# LED_STATUS.net
KiCad netlist of a schematic drawn in Altium Designer
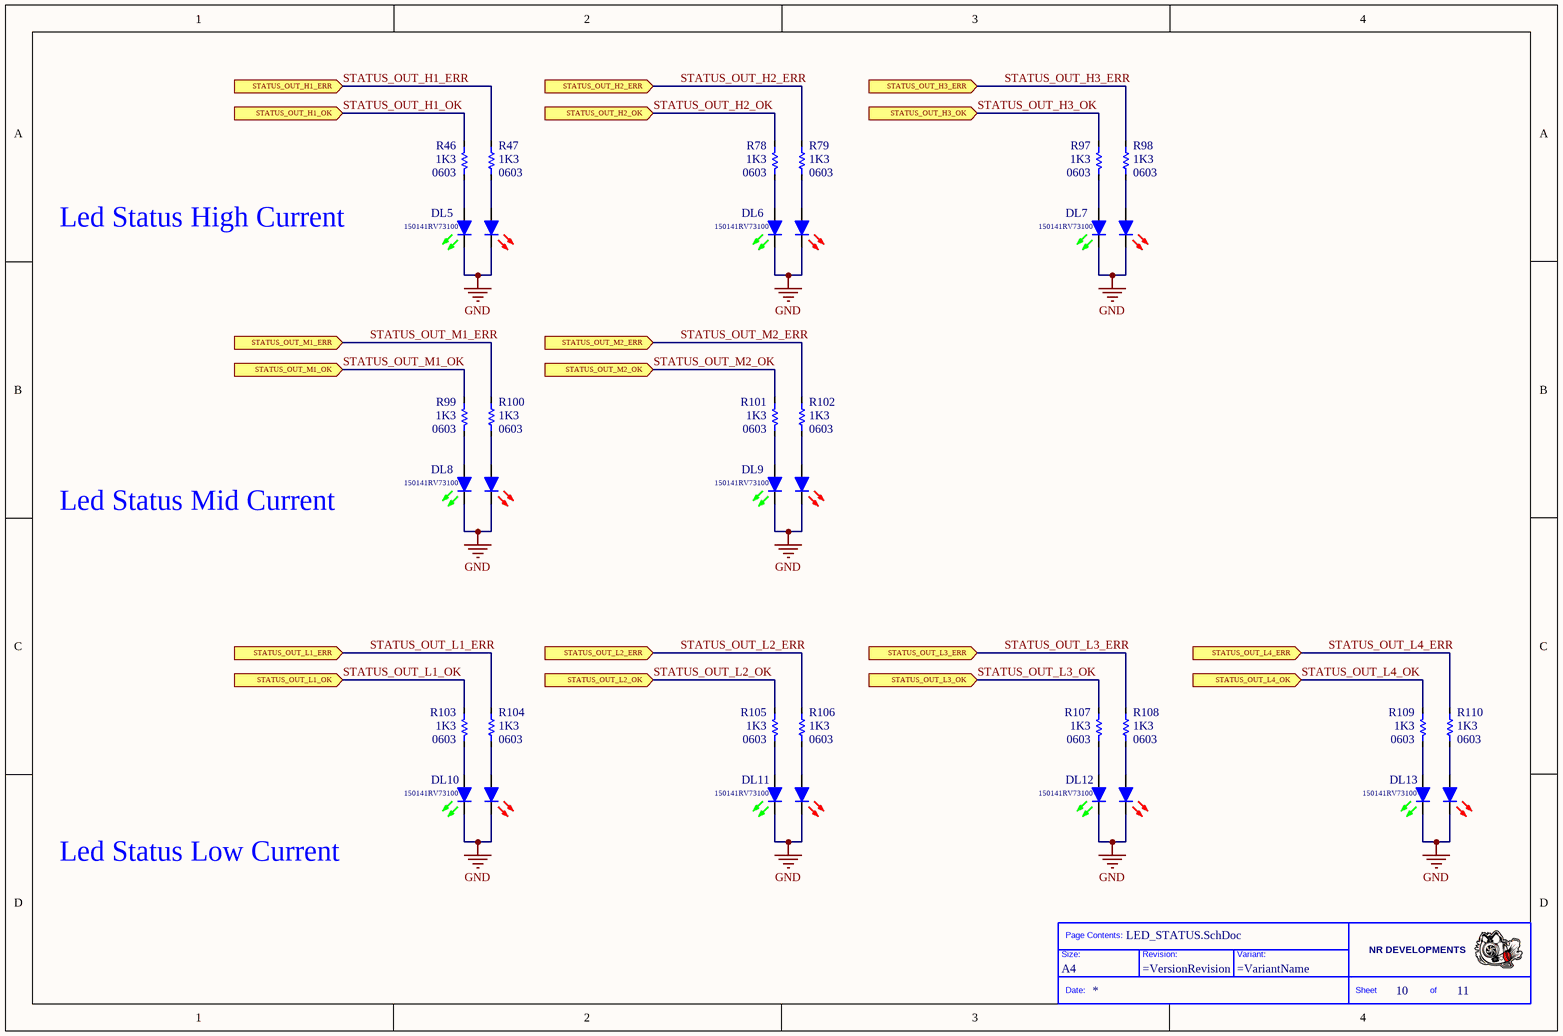
[diagram p0: LED_STATUS.SchDoc]

(export (version "E")
  (design (tool "Eeschema 10.0.6"))
  (components
    (comp (ref "*")
      (value "Title_Block")
      (fields (field (name "SIZE") "A4"))
      (libsource (lib "My_LIB") (part "Title_Block"))
    )
    (comp (ref "DL5")
      (value "150141RV73100")
      (footprint "WURTH-SBTW_3528")
      (description "Led Red - Green 3528")
      (fields (field (name "MANUFACTURER") "Wurth") (field (name "Comment") "LED_Red_Green"))
      (libsource (lib "My_LIB") (part "LED_Red_Green"))
    )
    (comp (ref "DL6")
      (value "150141RV73100")
      (footprint "WURTH-SBTW_3528")
      (description "Led Red - Green 3528")
      (fields (field (name "MANUFACTURER") "Wurth") (field (name "Comment") "LED_Red_Green"))
      (libsource (lib "My_LIB") (part "LED_Red_Green"))
    )
    (comp (ref "DL7")
      (value "150141RV73100")
      (footprint "WURTH-SBTW_3528")
      (description "Led Red - Green 3528")
      (fields (field (name "MANUFACTURER") "Wurth") (field (name "Comment") "LED_Red_Green"))
      (libsource (lib "My_LIB") (part "LED_Red_Green"))
    )
    (comp (ref "DL8")
      (value "150141RV73100")
      (footprint "WURTH-SBTW_3528")
      (description "Led Red - Green 3528")
      (fields (field (name "MANUFACTURER") "Wurth") (field (name "Comment") "LED_Red_Green"))
      (libsource (lib "My_LIB") (part "LED_Red_Green"))
    )
    (comp (ref "DL9")
      (value "150141RV73100")
      (footprint "WURTH-SBTW_3528")
      (description "Led Red - Green 3528")
      (fields (field (name "MANUFACTURER") "Wurth") (field (name "Comment") "LED_Red_Green"))
      (libsource (lib "My_LIB") (part "LED_Red_Green"))
    )
    (comp (ref "DL10")
      (value "150141RV73100")
      (footprint "WURTH-SBTW_3528")
      (description "Led Red - Green 3528")
      (fields (field (name "MANUFACTURER") "Wurth") (field (name "Comment") "LED_Red_Green"))
      (libsource (lib "My_LIB") (part "LED_Red_Green"))
    )
    (comp (ref "DL11")
      (value "150141RV73100")
      (footprint "WURTH-SBTW_3528")
      (description "Led Red - Green 3528")
      (fields (field (name "MANUFACTURER") "Wurth") (field (name "Comment") "LED_Red_Green"))
      (libsource (lib "My_LIB") (part "LED_Red_Green"))
    )
    (comp (ref "DL12")
      (value "150141RV73100")
      (footprint "WURTH-SBTW_3528")
      (description "Led Red - Green 3528")
      (fields (field (name "MANUFACTURER") "Wurth") (field (name "Comment") "LED_Red_Green"))
      (libsource (lib "My_LIB") (part "LED_Red_Green"))
    )
    (comp (ref "DL13")
      (value "150141RV73100")
      (footprint "WURTH-SBTW_3528")
      (description "Led Red - Green 3528")
      (fields (field (name "MANUFACTURER") "Wurth") (field (name "Comment") "LED_Red_Green"))
      (libsource (lib "My_LIB") (part "LED_Red_Green"))
    )
    (comp (ref "R46")
      (value "1K3")
      (footprint "RESC1608X06M")
      (fields
        (field (name "CASE") "0603")
        (field (name "MANUFACTURER") "Vishay")
        (field (name "PARTNUMBER") "RC0603FR-071K3L")
        (field (name "Comment") "Res")
      )
      (libsource (lib "My_LIB") (part "Resistor"))
    )
    (comp (ref "R47")
      (value "1K3")
      (footprint "RESC1608X06M")
      (fields
        (field (name "CASE") "0603")
        (field (name "MANUFACTURER") "Vishay")
        (field (name "PARTNUMBER") "RC0603FR-071K3L")
        (field (name "Comment") "Res")
      )
      (libsource (lib "My_LIB") (part "Resistor"))
    )
    (comp (ref "R78")
      (value "1K3")
      (footprint "RESC1608X06M")
      (fields
        (field (name "CASE") "0603")
        (field (name "MANUFACTURER") "Vishay")
        (field (name "PARTNUMBER") "RC0603FR-071K3L")
        (field (name "Comment") "Res")
      )
      (libsource (lib "My_LIB") (part "Resistor"))
    )
    (comp (ref "R79")
      (value "1K3")
      (footprint "RESC1608X06M")
      (fields
        (field (name "CASE") "0603")
        (field (name "MANUFACTURER") "Vishay")
        (field (name "PARTNUMBER") "RC0603FR-071K3L")
        (field (name "Comment") "Res")
      )
      (libsource (lib "My_LIB") (part "Resistor"))
    )
    (comp (ref "R97")
      (value "1K3")
      (footprint "RESC1608X06M")
      (fields
        (field (name "CASE") "0603")
        (field (name "MANUFACTURER") "Vishay")
        (field (name "PARTNUMBER") "RC0603FR-071K3L")
        (field (name "Comment") "Res")
      )
      (libsource (lib "My_LIB") (part "Resistor"))
    )
    (comp (ref "R98")
      (value "1K3")
      (footprint "RESC1608X06M")
      (fields
        (field (name "CASE") "0603")
        (field (name "MANUFACTURER") "Vishay")
        (field (name "PARTNUMBER") "RC0603FR-071K3L")
        (field (name "Comment") "Res")
      )
      (libsource (lib "My_LIB") (part "Resistor"))
    )
    (comp (ref "R99")
      (value "1K3")
      (footprint "RESC1608X06M")
      (fields
        (field (name "CASE") "0603")
        (field (name "MANUFACTURER") "Vishay")
        (field (name "PARTNUMBER") "RC0603FR-071K3L")
        (field (name "Comment") "Res")
      )
      (libsource (lib "My_LIB") (part "Resistor"))
    )
    (comp (ref "R100")
      (value "1K3")
      (footprint "RESC1608X06M")
      (fields
        (field (name "CASE") "0603")
        (field (name "MANUFACTURER") "Vishay")
        (field (name "PARTNUMBER") "RC0603FR-071K3L")
        (field (name "Comment") "Res")
      )
      (libsource (lib "My_LIB") (part "Resistor"))
    )
    (comp (ref "R101")
      (value "1K3")
      (footprint "RESC1608X06M")
      (fields
        (field (name "CASE") "0603")
        (field (name "MANUFACTURER") "Vishay")
        (field (name "PARTNUMBER") "RC0603FR-071K3L")
        (field (name "Comment") "Res")
      )
      (libsource (lib "My_LIB") (part "Resistor"))
    )
    (comp (ref "R102")
      (value "1K3")
      (footprint "RESC1608X06M")
      (fields
        (field (name "CASE") "0603")
        (field (name "MANUFACTURER") "Vishay")
        (field (name "PARTNUMBER") "RC0603FR-071K3L")
        (field (name "Comment") "Res")
      )
      (libsource (lib "My_LIB") (part "Resistor"))
    )
    (comp (ref "R103")
      (value "1K3")
      (footprint "RESC1608X06M")
      (fields
        (field (name "CASE") "0603")
        (field (name "MANUFACTURER") "Vishay")
        (field (name "PARTNUMBER") "RC0603FR-071K3L")
        (field (name "Comment") "Res")
      )
      (libsource (lib "My_LIB") (part "Resistor"))
    )
    (comp (ref "R104")
      (value "1K3")
      (footprint "RESC1608X06M")
      (fields
        (field (name "CASE") "0603")
        (field (name "MANUFACTURER") "Vishay")
        (field (name "PARTNUMBER") "RC0603FR-071K3L")
        (field (name "Comment") "Res")
      )
      (libsource (lib "My_LIB") (part "Resistor"))
    )
    (comp (ref "R105")
      (value "1K3")
      (footprint "RESC1608X06M")
      (fields
        (field (name "CASE") "0603")
        (field (name "MANUFACTURER") "Vishay")
        (field (name "PARTNUMBER") "RC0603FR-071K3L")
        (field (name "Comment") "Res")
      )
      (libsource (lib "My_LIB") (part "Resistor"))
    )
    (comp (ref "R106")
      (value "1K3")
      (footprint "RESC1608X06M")
      (fields
        (field (name "CASE") "0603")
        (field (name "MANUFACTURER") "Vishay")
        (field (name "PARTNUMBER") "RC0603FR-071K3L")
        (field (name "Comment") "Res")
      )
      (libsource (lib "My_LIB") (part "Resistor"))
    )
    (comp (ref "R107")
      (value "1K3")
      (footprint "RESC1608X06M")
      (fields
        (field (name "CASE") "0603")
        (field (name "MANUFACTURER") "Vishay")
        (field (name "PARTNUMBER") "RC0603FR-071K3L")
        (field (name "Comment") "Res")
      )
      (libsource (lib "My_LIB") (part "Resistor"))
    )
    (comp (ref "R108")
      (value "1K3")
      (footprint "RESC1608X06M")
      (fields
        (field (name "CASE") "0603")
        (field (name "MANUFACTURER") "Vishay")
        (field (name "PARTNUMBER") "RC0603FR-071K3L")
        (field (name "Comment") "Res")
      )
      (libsource (lib "My_LIB") (part "Resistor"))
    )
    (comp (ref "R109")
      (value "1K3")
      (footprint "RESC1608X06M")
      (fields
        (field (name "CASE") "0603")
        (field (name "MANUFACTURER") "Vishay")
        (field (name "PARTNUMBER") "RC0603FR-071K3L")
        (field (name "Comment") "Res")
      )
      (libsource (lib "My_LIB") (part "Resistor"))
    )
    (comp (ref "R110")
      (value "1K3")
      (footprint "RESC1608X06M")
      (fields
        (field (name "CASE") "0603")
        (field (name "MANUFACTURER") "Vishay")
        (field (name "PARTNUMBER") "RC0603FR-071K3L")
        (field (name "Comment") "Res")
      )
      (libsource (lib "My_LIB") (part "Resistor"))
    )
  )
  (nets
    (net (code "1") (name "/STATUS_OUT_H1_ERR") (class "Default")
      (node (ref "R47") (pin "2") (pinfunction "2_2") (pintype "passive"))
    )
    (net (code "2") (name "/STATUS_OUT_H1_OK") (class "Default")
      (node (ref "R46") (pin "2") (pinfunction "2_2") (pintype "passive"))
    )
    (net (code "3") (name "/STATUS_OUT_H2_ERR") (class "Default")
      (node (ref "R79") (pin "2") (pinfunction "2_2") (pintype "passive"))
    )
    (net (code "4") (name "/STATUS_OUT_H2_OK") (class "Default")
      (node (ref "R78") (pin "2") (pinfunction "2_2") (pintype "passive"))
    )
    (net (code "5") (name "/STATUS_OUT_H3_ERR") (class "Default")
      (node (ref "R98") (pin "2") (pinfunction "2_2") (pintype "passive"))
    )
    (net (code "6") (name "/STATUS_OUT_H3_OK") (class "Default")
      (node (ref "R97") (pin "2") (pinfunction "2_2") (pintype "passive"))
    )
    (net (code "7") (name "/STATUS_OUT_L1_ERR") (class "Default")
      (node (ref "R104") (pin "2") (pinfunction "2_2") (pintype "passive"))
    )
    (net (code "8") (name "/STATUS_OUT_L1_OK") (class "Default")
      (node (ref "R103") (pin "2") (pinfunction "2_2") (pintype "passive"))
    )
    (net (code "9") (name "/STATUS_OUT_L2_ERR") (class "Default")
      (node (ref "R106") (pin "2") (pinfunction "2_2") (pintype "passive"))
    )
    (net (code "10") (name "/STATUS_OUT_L2_OK") (class "Default")
      (node (ref "R105") (pin "2") (pinfunction "2_2") (pintype "passive"))
    )
    (net (code "11") (name "/STATUS_OUT_L3_ERR") (class "Default")
      (node (ref "R108") (pin "2") (pinfunction "2_2") (pintype "passive"))
    )
    (net (code "12") (name "/STATUS_OUT_L3_OK") (class "Default")
      (node (ref "R107") (pin "2") (pinfunction "2_2") (pintype "passive"))
    )
    (net (code "13") (name "/STATUS_OUT_L4_ERR") (class "Default")
      (node (ref "R110") (pin "2") (pinfunction "2_2") (pintype "passive"))
    )
    (net (code "14") (name "/STATUS_OUT_L4_OK") (class "Default")
      (node (ref "R109") (pin "2") (pinfunction "2_2") (pintype "passive"))
    )
    (net (code "15") (name "/STATUS_OUT_M1_ERR") (class "Default")
      (node (ref "R100") (pin "2") (pinfunction "2_2") (pintype "passive"))
    )
    (net (code "16") (name "/STATUS_OUT_M1_OK") (class "Default")
      (node (ref "R99") (pin "2") (pinfunction "2_2") (pintype "passive"))
    )
    (net (code "17") (name "/STATUS_OUT_M2_ERR") (class "Default")
      (node (ref "R102") (pin "2") (pinfunction "2_2") (pintype "passive"))
    )
    (net (code "18") (name "/STATUS_OUT_M2_OK") (class "Default")
      (node (ref "R101") (pin "2") (pinfunction "2_2") (pintype "passive"))
    )
    (net (code "19") (name "GND") (class "Default")
      (node (ref "DL10") (pin "C1") (pinfunction "C1_C1") (pintype "passive"))
      (node (ref "DL10") (pin "C2") (pinfunction "C2_C2") (pintype "passive"))
      (node (ref "DL11") (pin "C1") (pinfunction "C1_C1") (pintype "passive"))
      (node (ref "DL11") (pin "C2") (pinfunction "C2_C2") (pintype "passive"))
      (node (ref "DL12") (pin "C1") (pinfunction "C1_C1") (pintype "passive"))
      (node (ref "DL12") (pin "C2") (pinfunction "C2_C2") (pintype "passive"))
      (node (ref "DL13") (pin "C1") (pinfunction "C1_C1") (pintype "passive"))
      (node (ref "DL13") (pin "C2") (pinfunction "C2_C2") (pintype "passive"))
      (node (ref "DL5") (pin "C1") (pinfunction "C1_C1") (pintype "passive"))
      (node (ref "DL5") (pin "C2") (pinfunction "C2_C2") (pintype "passive"))
      (node (ref "DL6") (pin "C1") (pinfunction "C1_C1") (pintype "passive"))
      (node (ref "DL6") (pin "C2") (pinfunction "C2_C2") (pintype "passive"))
      (node (ref "DL7") (pin "C1") (pinfunction "C1_C1") (pintype "passive"))
      (node (ref "DL7") (pin "C2") (pinfunction "C2_C2") (pintype "passive"))
      (node (ref "DL8") (pin "C1") (pinfunction "C1_C1") (pintype "passive"))
      (node (ref "DL8") (pin "C2") (pinfunction "C2_C2") (pintype "passive"))
      (node (ref "DL9") (pin "C1") (pinfunction "C1_C1") (pintype "passive"))
      (node (ref "DL9") (pin "C2") (pinfunction "C2_C2") (pintype "passive"))
    )
    (net (code "20") (name "Net-(DL5-PadA1)") (class "Default")
      (node (ref "DL5") (pin "A1") (pinfunction "A1_A1") (pintype "passive"))
      (node (ref "R47") (pin "1") (pinfunction "1_1") (pintype "passive"))
    )
    (net (code "21") (name "Net-(DL5-PadA2)") (class "Default")
      (node (ref "DL5") (pin "A2") (pinfunction "A2_A2") (pintype "passive"))
      (node (ref "R46") (pin "1") (pinfunction "1_1") (pintype "passive"))
    )
    (net (code "22") (name "Net-(DL6-PadA1)") (class "Default")
      (node (ref "DL6") (pin "A1") (pinfunction "A1_A1") (pintype "passive"))
      (node (ref "R79") (pin "1") (pinfunction "1_1") (pintype "passive"))
    )
    (net (code "23") (name "Net-(DL6-PadA2)") (class "Default")
      (node (ref "DL6") (pin "A2") (pinfunction "A2_A2") (pintype "passive"))
      (node (ref "R78") (pin "1") (pinfunction "1_1") (pintype "passive"))
    )
    (net (code "24") (name "Net-(DL7-PadA1)") (class "Default")
      (node (ref "DL7") (pin "A1") (pinfunction "A1_A1") (pintype "passive"))
      (node (ref "R98") (pin "1") (pinfunction "1_1") (pintype "passive"))
    )
    (net (code "25") (name "Net-(DL7-PadA2)") (class "Default")
      (node (ref "DL7") (pin "A2") (pinfunction "A2_A2") (pintype "passive"))
      (node (ref "R97") (pin "1") (pinfunction "1_1") (pintype "passive"))
    )
    (net (code "26") (name "Net-(DL8-PadA1)") (class "Default")
      (node (ref "DL8") (pin "A1") (pinfunction "A1_A1") (pintype "passive"))
      (node (ref "R100") (pin "1") (pinfunction "1_1") (pintype "passive"))
    )
    (net (code "27") (name "Net-(DL8-PadA2)") (class "Default")
      (node (ref "DL8") (pin "A2") (pinfunction "A2_A2") (pintype "passive"))
      (node (ref "R99") (pin "1") (pinfunction "1_1") (pintype "passive"))
    )
    (net (code "28") (name "Net-(DL9-PadA1)") (class "Default")
      (node (ref "DL9") (pin "A1") (pinfunction "A1_A1") (pintype "passive"))
      (node (ref "R102") (pin "1") (pinfunction "1_1") (pintype "passive"))
    )
    (net (code "29") (name "Net-(DL9-PadA2)") (class "Default")
      (node (ref "DL9") (pin "A2") (pinfunction "A2_A2") (pintype "passive"))
      (node (ref "R101") (pin "1") (pinfunction "1_1") (pintype "passive"))
    )
    (net (code "30") (name "Net-(DL10-PadA1)") (class "Default")
      (node (ref "DL10") (pin "A1") (pinfunction "A1_A1") (pintype "passive"))
      (node (ref "R104") (pin "1") (pinfunction "1_1") (pintype "passive"))
    )
    (net (code "31") (name "Net-(DL10-PadA2)") (class "Default")
      (node (ref "DL10") (pin "A2") (pinfunction "A2_A2") (pintype "passive"))
      (node (ref "R103") (pin "1") (pinfunction "1_1") (pintype "passive"))
    )
    (net (code "32") (name "Net-(DL11-PadA1)") (class "Default")
      (node (ref "DL11") (pin "A1") (pinfunction "A1_A1") (pintype "passive"))
      (node (ref "R106") (pin "1") (pinfunction "1_1") (pintype "passive"))
    )
    (net (code "33") (name "Net-(DL11-PadA2)") (class "Default")
      (node (ref "DL11") (pin "A2") (pinfunction "A2_A2") (pintype "passive"))
      (node (ref "R105") (pin "1") (pinfunction "1_1") (pintype "passive"))
    )
    (net (code "34") (name "Net-(DL12-PadA1)") (class "Default")
      (node (ref "DL12") (pin "A1") (pinfunction "A1_A1") (pintype "passive"))
      (node (ref "R108") (pin "1") (pinfunction "1_1") (pintype "passive"))
    )
    (net (code "35") (name "Net-(DL12-PadA2)") (class "Default")
      (node (ref "DL12") (pin "A2") (pinfunction "A2_A2") (pintype "passive"))
      (node (ref "R107") (pin "1") (pinfunction "1_1") (pintype "passive"))
    )
    (net (code "36") (name "Net-(DL13-PadA1)") (class "Default")
      (node (ref "DL13") (pin "A1") (pinfunction "A1_A1") (pintype "passive"))
      (node (ref "R110") (pin "1") (pinfunction "1_1") (pintype "passive"))
    )
    (net (code "37") (name "Net-(DL13-PadA2)") (class "Default")
      (node (ref "DL13") (pin "A2") (pinfunction "A2_A2") (pintype "passive"))
      (node (ref "R109") (pin "1") (pinfunction "1_1") (pintype "passive"))
    )
  )
)
